# Smart_Charger_connection_plate.net
KiCad netlist of a schematic drawn in EasyEDA
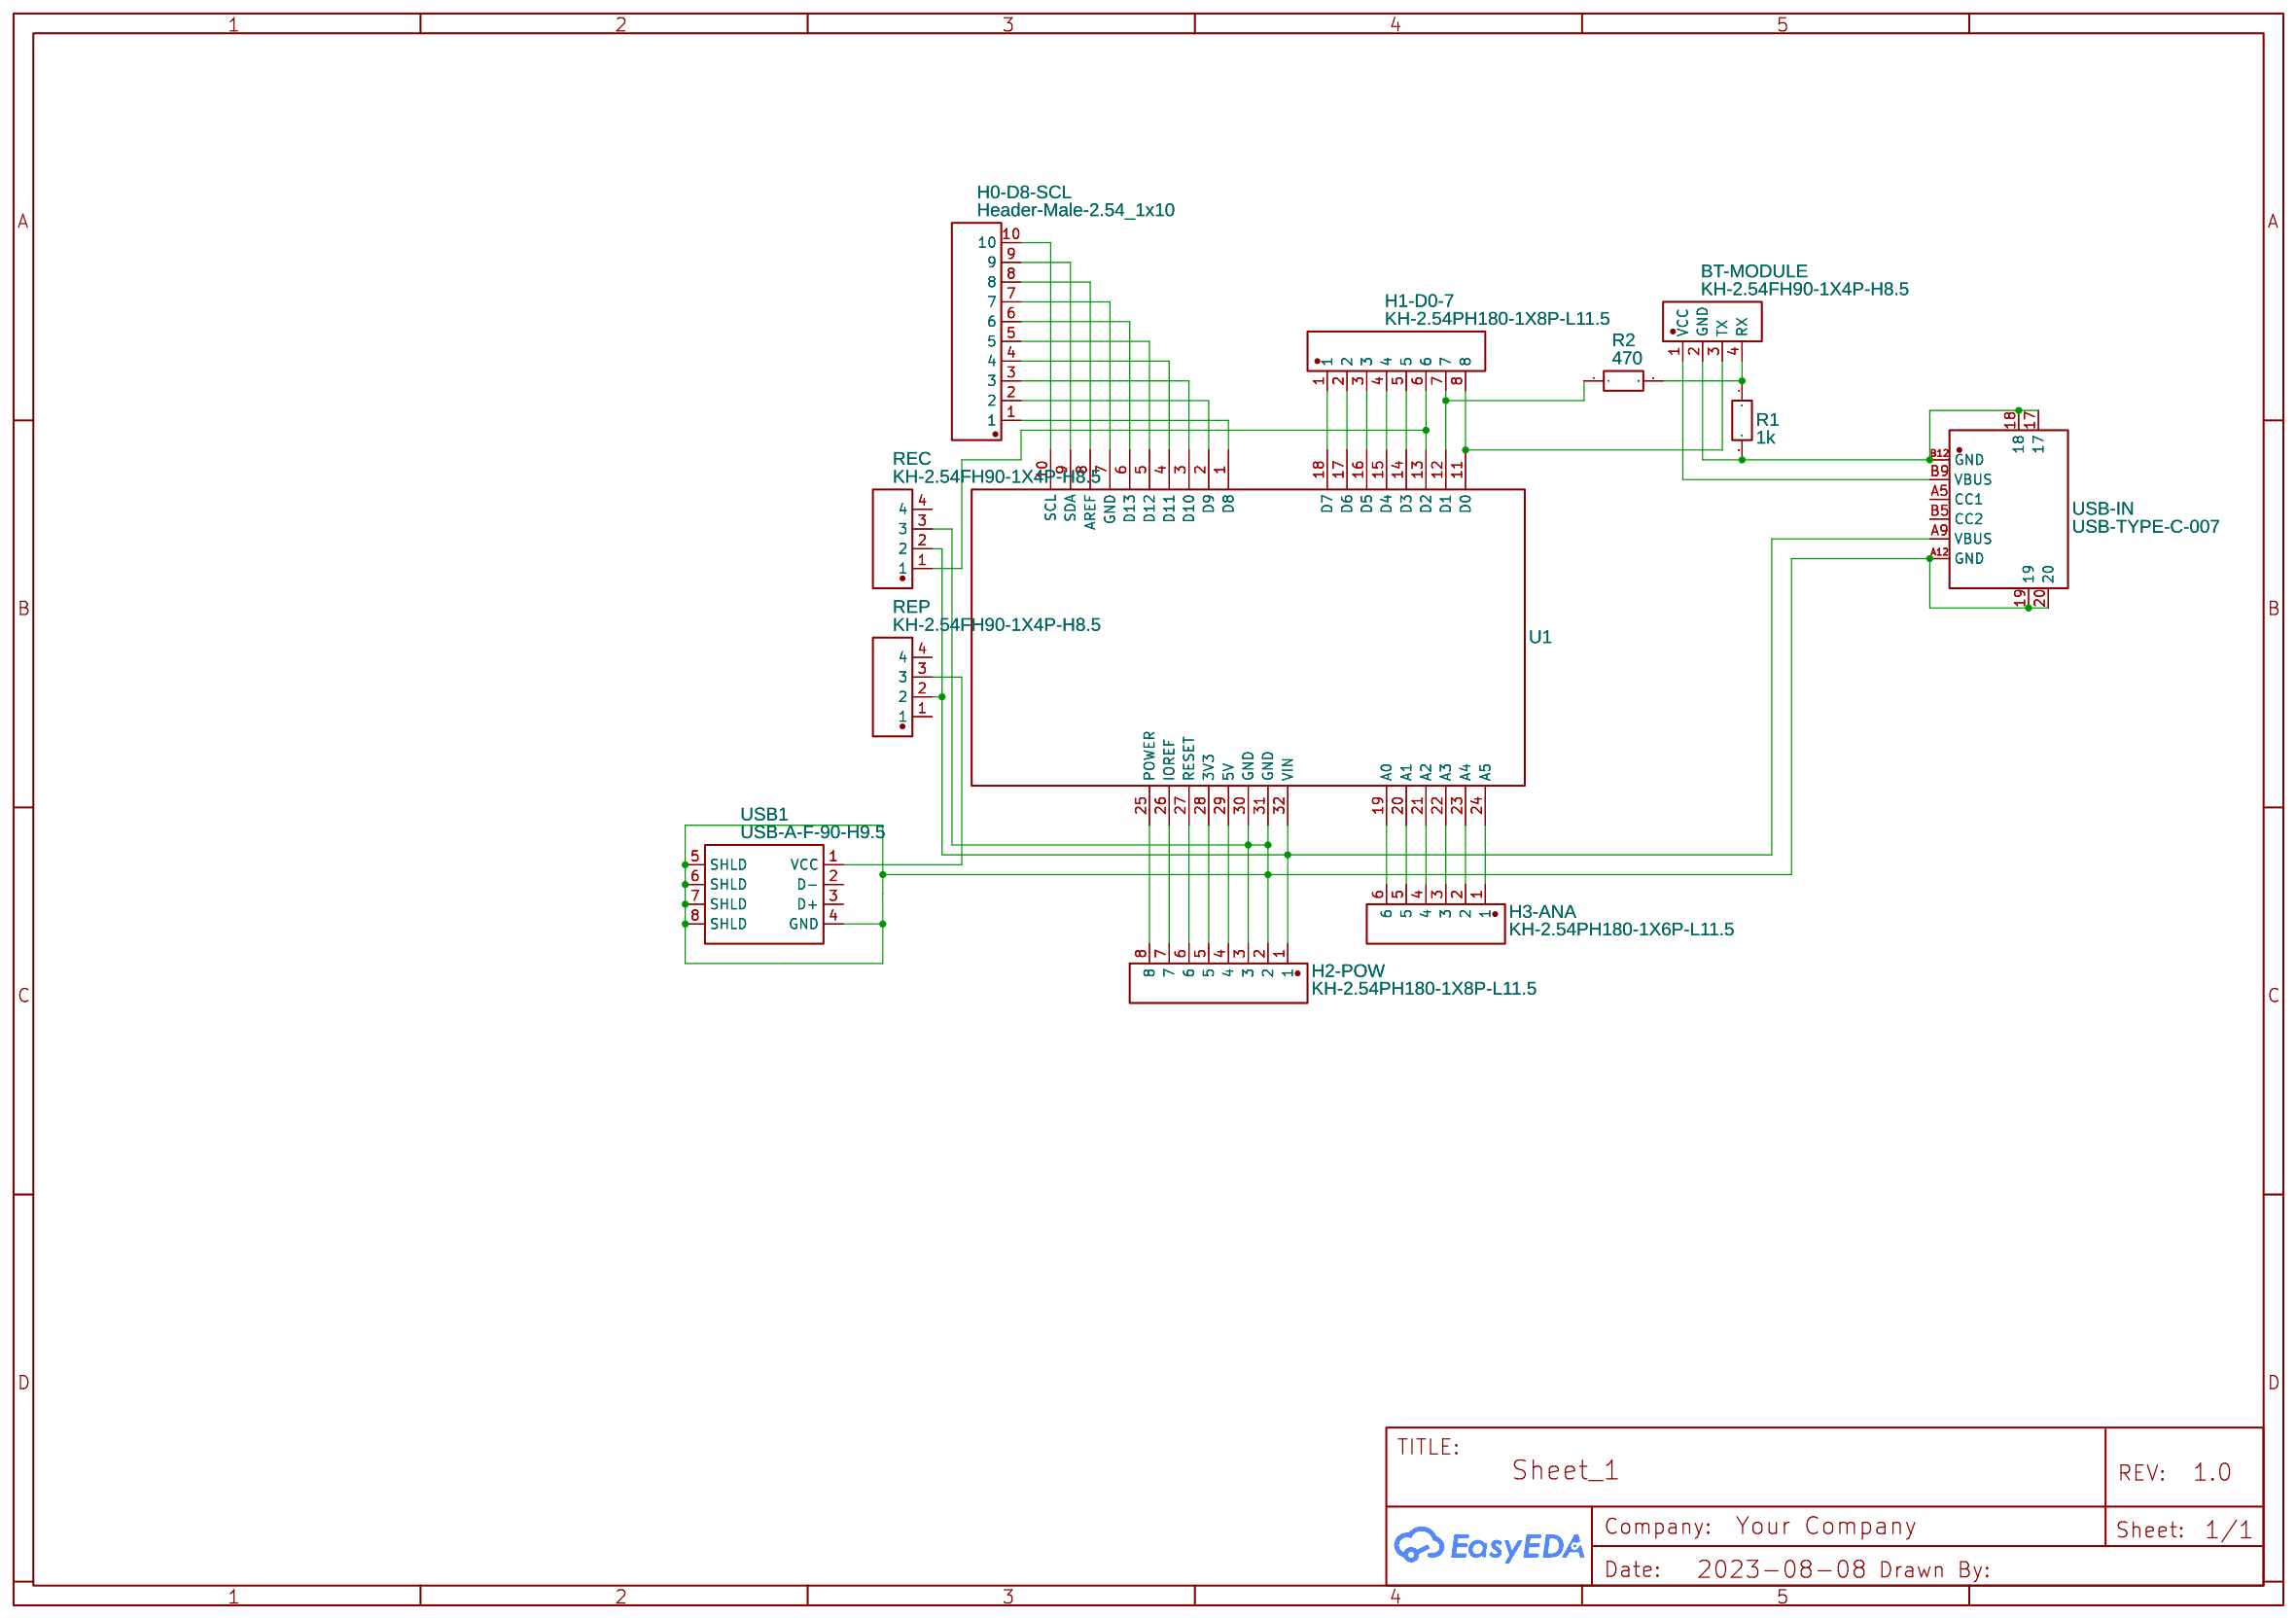
[diagram p0: schematic sheet]

(export (version "E")
  (design (tool "Eeschema 10.0.6"))
  (components
    (comp (ref "BT-MODULE")
      (value "KH-2.54FH90-1X4P-H8.5")
      (fields (field (name "Manufacturer") "kinghelm(金航标)"))
      (libsource (lib "") (part "KH-2.54FH90-1X4P-H8.5_2"))
    )
    (comp (ref "H0-D8-SCL")
      (value "Header-Male-2.54_1x10")
      (fields (field (name "Manufacturer Part") "2.54-1*10P针") (field (name "Manufacturer") "BOOMELE(博穆精密)"))
      (libsource (lib "") (part "Header-Male-2.54_1x10"))
    )
    (comp (ref "H1-D0-7")
      (value "KH-2.54PH180-1X8P-L11.5")
      (fields (field (name "Manufacturer") "kinghelm(金航标)"))
      (libsource (lib "") (part "KH-2.54PH180-1X8P-L11.5_1"))
    )
    (comp (ref "H2-POW")
      (value "KH-2.54PH180-1X8P-L11.5")
      (fields (field (name "Manufacturer") "kinghelm(金航标)"))
      (libsource (lib "") (part "KH-2.54PH180-1X8P-L11.5"))
    )
    (comp (ref "H3-ANA")
      (value "KH-2.54PH180-1X6P-L11.5")
      (fields (field (name "Manufacturer") "kinghelm(金航标)"))
      (libsource (lib "") (part "KH-2.54PH180-1X6P-L11.5"))
    )
    (comp (ref "R1") (value "1k") (libsource (lib "") (part "R_0603_EU_1")))
    (comp (ref "R2") (value "470") (libsource (lib "") (part "R_0603_EU")))
    (comp (ref "REC")
      (value "KH-2.54FH90-1X4P-H8.5")
      (fields (field (name "Manufacturer") "kinghelm(金航标)"))
      (libsource (lib "") (part "KH-2.54FH90-1X4P-H8.5"))
    )
    (comp (ref "REP")
      (value "KH-2.54FH90-1X4P-H8.5")
      (fields (field (name "Manufacturer") "kinghelm(金航标)"))
      (libsource (lib "") (part "KH-2.54FH90-1X4P-H8.5_1"))
    )
    (comp (ref "U1") (value "NO") (libsource (lib "") (part "UNO_R3")))
    (comp (ref "USB-IN")
      (value "USB-TYPE-C-007")
      (fields (field (name "Manufacturer") "DEALON(德艺隆)"))
      (libsource (lib "") (part "USB-TYPE-C-007"))
    )
    (comp (ref "USB1")
      (value "USB-A-F-90-H9.5")
      (fields (field (name "Manufacturer") "LCSC"))
      (libsource (lib "") (part "USB-A-F-90-H9.5"))
    )
  )
  (nets
    (net (code "1") (name "Net-(BT-MODULE-GND)") (class "Default")
      (node (ref "BT-MODULE") (pin "2") (pinfunction "GND_2") (pintype "unspecified"))
      (node (ref "R1") (pin "2") (pinfunction "2_2") (pintype "unspecified"))
      (node (ref "USB-IN") (pin "17") (pinfunction "17_17") (pintype "unspecified"))
      (node (ref "USB-IN") (pin "18") (pinfunction "18_18") (pintype "unspecified"))
      (node (ref "USB-IN") (pin "B12") (pinfunction "GND_B12") (pintype "unspecified"))
    )
    (net (code "2") (name "Net-(BT-MODULE-RX)") (class "Default")
      (node (ref "BT-MODULE") (pin "4") (pinfunction "RX_4") (pintype "unspecified"))
      (node (ref "R1") (pin "1") (pinfunction "1_1") (pintype "unspecified"))
      (node (ref "R2") (pin "2") (pinfunction "2_2") (pintype "unspecified"))
    )
    (net (code "3") (name "Net-(BT-MODULE-TX)") (class "Default")
      (node (ref "BT-MODULE") (pin "3") (pinfunction "TX_3") (pintype "unspecified"))
      (node (ref "H1-D0-7") (pin "8") (pinfunction "8_8") (pintype "unspecified"))
      (node (ref "U1") (pin "11") (pinfunction "D0_11") (pintype "unspecified"))
    )
    (net (code "4") (name "Net-(BT-MODULE-VCC)") (class "Default")
      (node (ref "BT-MODULE") (pin "1") (pinfunction "VCC_1") (pintype "unspecified"))
      (node (ref "USB-IN") (pin "B9") (pinfunction "VBUS_B9") (pintype "unspecified"))
    )
    (net (code "5") (name "Net-(H0-D8-SCL-Pad7)") (class "Default")
      (node (ref "H0-D8-SCL") (pin "7") (pinfunction "7_7") (pintype "unspecified"))
      (node (ref "U1") (pin "7") (pinfunction "GND_7") (pintype "unspecified"))
    )
    (net (code "6") (name "Net-(U1-3V3)") (class "Default")
      (node (ref "H2-POW") (pin "5") (pinfunction "5_5") (pintype "unspecified"))
      (node (ref "U1") (pin "28") (pinfunction "3V3_28") (pintype "unspecified"))
    )
    (net (code "7") (name "Net-(U1-5V)") (class "Default")
      (node (ref "H2-POW") (pin "4") (pinfunction "4_4") (pintype "unspecified"))
      (node (ref "U1") (pin "29") (pinfunction "5V_29") (pintype "unspecified"))
    )
    (net (code "8") (name "Net-(U1-A0)") (class "Default")
      (node (ref "H3-ANA") (pin "6") (pinfunction "6_6") (pintype "unspecified"))
      (node (ref "U1") (pin "19") (pinfunction "A0_19") (pintype "unspecified"))
    )
    (net (code "9") (name "Net-(U1-A1)") (class "Default")
      (node (ref "H3-ANA") (pin "5") (pinfunction "5_5") (pintype "unspecified"))
      (node (ref "U1") (pin "20") (pinfunction "A1_20") (pintype "unspecified"))
    )
    (net (code "10") (name "Net-(U1-A2)") (class "Default")
      (node (ref "H3-ANA") (pin "4") (pinfunction "4_4") (pintype "unspecified"))
      (node (ref "U1") (pin "21") (pinfunction "A2_21") (pintype "unspecified"))
    )
    (net (code "11") (name "Net-(U1-A3)") (class "Default")
      (node (ref "H3-ANA") (pin "3") (pinfunction "3_3") (pintype "unspecified"))
      (node (ref "U1") (pin "22") (pinfunction "A3_22") (pintype "unspecified"))
    )
    (net (code "12") (name "Net-(U1-A4)") (class "Default")
      (node (ref "H3-ANA") (pin "2") (pinfunction "2_2") (pintype "unspecified"))
      (node (ref "U1") (pin "23") (pinfunction "A4_23") (pintype "unspecified"))
    )
    (net (code "13") (name "Net-(U1-A5)") (class "Default")
      (node (ref "H3-ANA") (pin "1") (pinfunction "1_1") (pintype "unspecified"))
      (node (ref "U1") (pin "24") (pinfunction "A5_24") (pintype "unspecified"))
    )
    (net (code "14") (name "Net-(U1-AREF)") (class "Default")
      (node (ref "H0-D8-SCL") (pin "8") (pinfunction "8_8") (pintype "unspecified"))
      (node (ref "U1") (pin "8") (pinfunction "AREF_8") (pintype "unspecified"))
    )
    (net (code "15") (name "Net-(U1-D1)") (class "Default")
      (node (ref "H1-D0-7") (pin "7") (pinfunction "7_7") (pintype "unspecified"))
      (node (ref "R2") (pin "1") (pinfunction "1_1") (pintype "unspecified"))
      (node (ref "U1") (pin "12") (pinfunction "D1_12") (pintype "unspecified"))
    )
    (net (code "16") (name "Net-(U1-D2)") (class "Default")
      (node (ref "H1-D0-7") (pin "6") (pinfunction "6_6") (pintype "unspecified"))
      (node (ref "REC") (pin "1") (pinfunction "1_1") (pintype "unspecified"))
      (node (ref "U1") (pin "13") (pinfunction "D2_13") (pintype "unspecified"))
    )
    (net (code "17") (name "Net-(U1-D3)") (class "Default")
      (node (ref "H1-D0-7") (pin "5") (pinfunction "5_5") (pintype "unspecified"))
      (node (ref "U1") (pin "14") (pinfunction "D3_14") (pintype "unspecified"))
    )
    (net (code "18") (name "Net-(U1-D4)") (class "Default")
      (node (ref "H1-D0-7") (pin "4") (pinfunction "4_4") (pintype "unspecified"))
      (node (ref "U1") (pin "15") (pinfunction "D4_15") (pintype "unspecified"))
    )
    (net (code "19") (name "Net-(U1-D5)") (class "Default")
      (node (ref "H1-D0-7") (pin "3") (pinfunction "3_3") (pintype "unspecified"))
      (node (ref "U1") (pin "16") (pinfunction "D5_16") (pintype "unspecified"))
    )
    (net (code "20") (name "Net-(U1-D6)") (class "Default")
      (node (ref "H1-D0-7") (pin "2") (pinfunction "2_2") (pintype "unspecified"))
      (node (ref "U1") (pin "17") (pinfunction "D6_17") (pintype "unspecified"))
    )
    (net (code "21") (name "Net-(U1-D7)") (class "Default")
      (node (ref "H1-D0-7") (pin "1") (pinfunction "1_1") (pintype "unspecified"))
      (node (ref "U1") (pin "18") (pinfunction "D7_18") (pintype "unspecified"))
    )
    (net (code "22") (name "Net-(U1-D8)") (class "Default")
      (node (ref "H0-D8-SCL") (pin "1") (pinfunction "1_1") (pintype "unspecified"))
      (node (ref "U1") (pin "1") (pinfunction "D8_1") (pintype "unspecified"))
    )
    (net (code "23") (name "Net-(U1-D9)") (class "Default")
      (node (ref "H0-D8-SCL") (pin "2") (pinfunction "2_2") (pintype "unspecified"))
      (node (ref "U1") (pin "2") (pinfunction "D9_2") (pintype "unspecified"))
    )
    (net (code "24") (name "Net-(U1-D10)") (class "Default")
      (node (ref "H0-D8-SCL") (pin "3") (pinfunction "3_3") (pintype "unspecified"))
      (node (ref "U1") (pin "3") (pinfunction "D10_3") (pintype "unspecified"))
    )
    (net (code "25") (name "Net-(U1-D11)") (class "Default")
      (node (ref "H0-D8-SCL") (pin "4") (pinfunction "4_4") (pintype "unspecified"))
      (node (ref "U1") (pin "4") (pinfunction "D11_4") (pintype "unspecified"))
    )
    (net (code "26") (name "Net-(U1-D12)") (class "Default")
      (node (ref "H0-D8-SCL") (pin "5") (pinfunction "5_5") (pintype "unspecified"))
      (node (ref "U1") (pin "5") (pinfunction "D12_5") (pintype "unspecified"))
    )
    (net (code "27") (name "Net-(U1-D13)") (class "Default")
      (node (ref "H0-D8-SCL") (pin "6") (pinfunction "6_6") (pintype "unspecified"))
      (node (ref "U1") (pin "6") (pinfunction "D13_6") (pintype "unspecified"))
    )
    (net (code "28") (name "Net-(U1-IOREF)") (class "Default")
      (node (ref "H2-POW") (pin "7") (pinfunction "7_7") (pintype "unspecified"))
      (node (ref "U1") (pin "26") (pinfunction "IOREF_26") (pintype "unspecified"))
    )
    (net (code "29") (name "Net-(U1-POWER)") (class "Default")
      (node (ref "H2-POW") (pin "8") (pinfunction "8_8") (pintype "unspecified"))
      (node (ref "U1") (pin "25") (pinfunction "POWER_25") (pintype "unspecified"))
    )
    (net (code "30") (name "Net-(U1-RESET)") (class "Default")
      (node (ref "H2-POW") (pin "6") (pinfunction "6_6") (pintype "unspecified"))
      (node (ref "U1") (pin "27") (pinfunction "RESET_27") (pintype "unspecified"))
    )
    (net (code "31") (name "Net-(U1-SCL)") (class "Default")
      (node (ref "H0-D8-SCL") (pin "10") (pinfunction "10_10") (pintype "unspecified"))
      (node (ref "U1") (pin "10") (pinfunction "SCL_10") (pintype "unspecified"))
    )
    (net (code "32") (name "Net-(U1-SDA)") (class "Default")
      (node (ref "H0-D8-SCL") (pin "9") (pinfunction "9_9") (pintype "unspecified"))
      (node (ref "U1") (pin "9") (pinfunction "SDA_9") (pintype "unspecified"))
    )
    (net (code "33") (name "Net-(U1-VIN)") (class "Default")
      (node (ref "H2-POW") (pin "1") (pinfunction "1_1") (pintype "unspecified"))
      (node (ref "REC") (pin "2") (pinfunction "2_2") (pintype "unspecified"))
      (node (ref "REP") (pin "2") (pinfunction "2_2") (pintype "unspecified"))
      (node (ref "U1") (pin "32") (pinfunction "VIN_32") (pintype "unspecified"))
      (node (ref "USB-IN") (pin "A9") (pinfunction "VBUS_A9") (pintype "unspecified"))
    )
    (net (code "34") (name "Net-(USB1-GND)") (class "Default")
      (node (ref "H2-POW") (pin "2") (pinfunction "2_2") (pintype "unspecified"))
      (node (ref "H2-POW") (pin "3") (pinfunction "3_3") (pintype "unspecified"))
      (node (ref "REC") (pin "3") (pinfunction "3_3") (pintype "unspecified"))
      (node (ref "U1") (pin "30") (pinfunction "GND_30") (pintype "unspecified"))
      (node (ref "U1") (pin "31") (pinfunction "GND_31") (pintype "unspecified"))
      (node (ref "USB-IN") (pin "19") (pinfunction "19_19") (pintype "unspecified"))
      (node (ref "USB-IN") (pin "20") (pinfunction "20_20") (pintype "unspecified"))
      (node (ref "USB-IN") (pin "A12") (pinfunction "GND_A12") (pintype "unspecified"))
      (node (ref "USB1") (pin "4") (pinfunction "GND_4") (pintype "input"))
      (node (ref "USB1") (pin "5") (pinfunction "SHLD_5") (pintype "unspecified"))
      (node (ref "USB1") (pin "6") (pinfunction "SHLD_6") (pintype "unspecified"))
      (node (ref "USB1") (pin "7") (pinfunction "SHLD_7") (pintype "unspecified"))
      (node (ref "USB1") (pin "8") (pinfunction "SHLD_8") (pintype "unspecified"))
    )
    (net (code "35") (name "Net-(USB1-VCC)") (class "Default")
      (node (ref "REP") (pin "3") (pinfunction "3_3") (pintype "unspecified"))
      (node (ref "USB1") (pin "1") (pinfunction "VCC_1") (pintype "input"))
    )
    (net (code "36") (name "unconnected-(REC-Pad4)") (class "Default")
      (node (ref "REC") (pin "4") (pinfunction "4_4") (pintype "unspecified"))
    )
    (net (code "37") (name "unconnected-(REP-Pad1)") (class "Default")
      (node (ref "REP") (pin "1") (pinfunction "1_1") (pintype "unspecified"))
    )
    (net (code "38") (name "unconnected-(REP-Pad4)") (class "Default")
      (node (ref "REP") (pin "4") (pinfunction "4_4") (pintype "unspecified"))
    )
    (net (code "39") (name "unconnected-(USB-IN-CC1-PadA5)") (class "Default")
      (node (ref "USB-IN") (pin "A5") (pinfunction "CC1_A5") (pintype "unspecified"))
    )
    (net (code "40") (name "unconnected-(USB-IN-CC2-PadB5)") (class "Default")
      (node (ref "USB-IN") (pin "B5") (pinfunction "CC2_B5") (pintype "unspecified"))
    )
    (net (code "41") (name "unconnected-(USB1-D+-Pad3)") (class "Default")
      (node (ref "USB1") (pin "3") (pinfunction "D+_3") (pintype "input"))
    )
    (net (code "42") (name "unconnected-(USB1-D--Pad2)") (class "Default")
      (node (ref "USB1") (pin "2") (pinfunction "D-_2") (pintype "input"))
    )
  )
)
